# supply_dual_v0_11_a0fac544.net
KiCad netlist of a schematic drawn in EAGLE
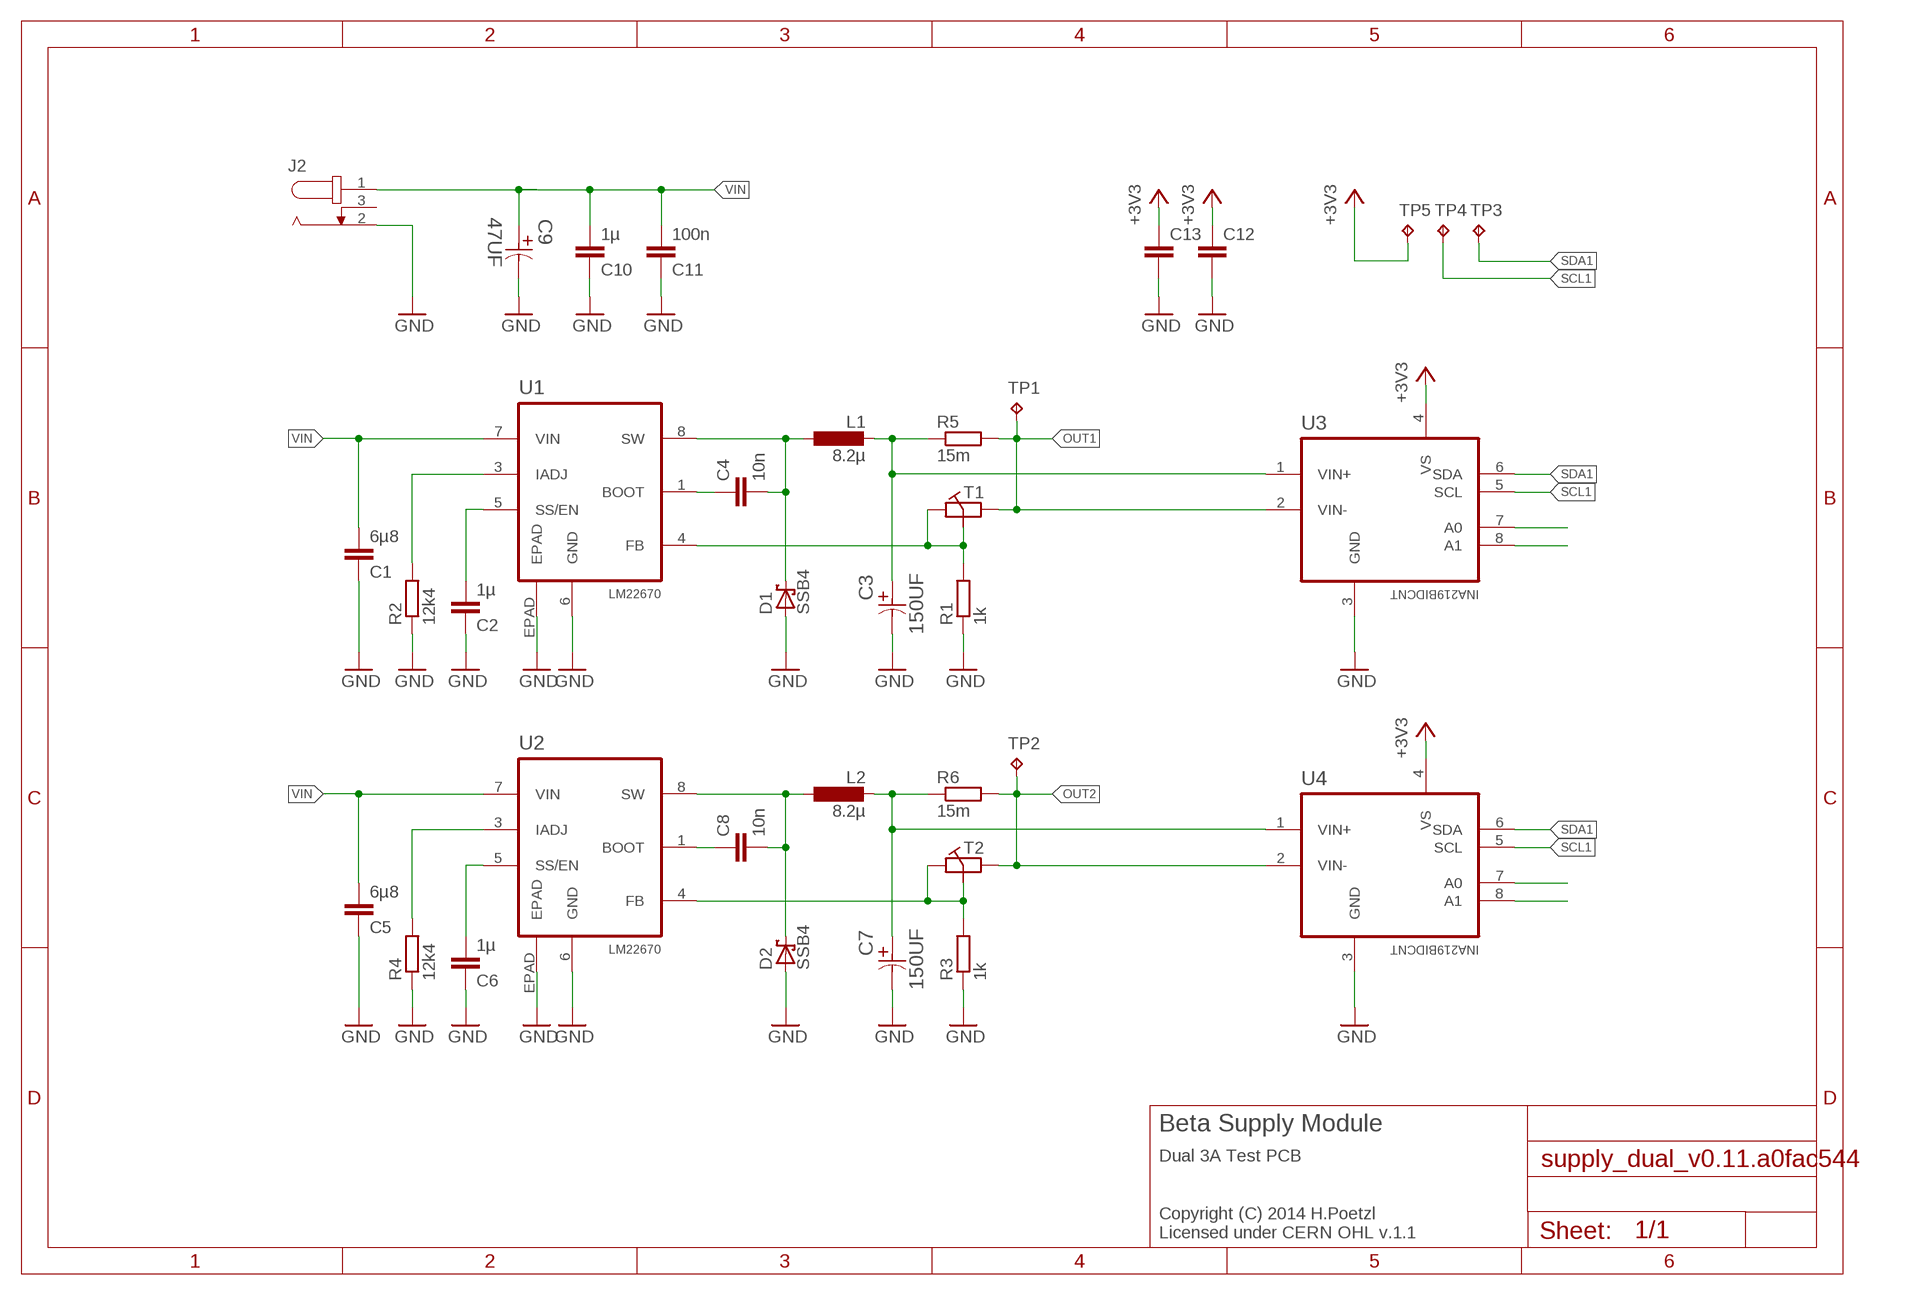
[diagram p0: schematic, sheet 1]

(export (version "E")
  (design (tool "Eeschema 10.0.6"))
  (components
    (comp (ref "C1")
      (value "6µ8")
      (footprint "eagle-import:C1210K")
      (libsource (lib "eagle-import") (part "C-EUC1210K"))
    )
    (comp (ref "C2")
      (value "1µ")
      (footprint "eagle-import:C0603K")
      (libsource (lib "eagle-import") (part "C-EUC0603K"))
    )
    (comp (ref "C3")
      (value "150UF")
      (footprint "eagle-import:CAPT7343X430N")
      (fields (field (name "MPN") "EEFCX0J151R"))
      (libsource (lib "eagle-import") (part "EEFCX0J151R"))
    )
    (comp (ref "C4")
      (value "10n")
      (footprint "eagle-import:C0603K")
      (libsource (lib "eagle-import") (part "C-EUC0603K"))
    )
    (comp (ref "C5")
      (value "6µ8")
      (footprint "eagle-import:C1210K")
      (libsource (lib "eagle-import") (part "C-EUC1210K"))
    )
    (comp (ref "C6")
      (value "1µ")
      (footprint "eagle-import:C0603K")
      (libsource (lib "eagle-import") (part "C-EUC0603K"))
    )
    (comp (ref "C7")
      (value "150UF")
      (footprint "eagle-import:CAPT7343X430N")
      (fields (field (name "MPN") "EEFCX0J151R"))
      (libsource (lib "eagle-import") (part "EEFCX0J151R"))
    )
    (comp (ref "C8")
      (value "10n")
      (footprint "eagle-import:C0603K")
      (libsource (lib "eagle-import") (part "C-EUC0603K"))
    )
    (comp (ref "C9")
      (value "47UF")
      (footprint "eagle-import:CAPAE660X610N")
      (fields (field (name "MPN") "EEE-FT1H470AP") (field (name "TOLERANCE") "±20 %"))
      (libsource (lib "eagle-import") (part "EEE--CASE-DFT1H470AP"))
    )
    (comp (ref "C10")
      (value "1µ")
      (footprint "eagle-import:C0805K")
      (libsource (lib "eagle-import") (part "C-EUC0805K"))
    )
    (comp (ref "C11")
      (value "100n")
      (footprint "eagle-import:C0603K")
      (libsource (lib "eagle-import") (part "C-EUC0603K"))
    )
    (comp (ref "C12")
      (value "C-EUC0402K")
      (footprint "eagle-import:C0402K")
      (libsource (lib "eagle-import") (part "C-EUC0402K"))
    )
    (comp (ref "C13")
      (value "C-EUC0402K")
      (footprint "eagle-import:C0402K")
      (libsource (lib "eagle-import") (part "C-EUC0402K"))
    )
    (comp (ref "D1")
      (value "SSB4")
      (footprint "eagle-import:DO-214AA")
      (libsource (lib "eagle-import") (part "SSB4"))
    )
    (comp (ref "D2")
      (value "SSB4")
      (footprint "eagle-import:DO-214AA")
      (libsource (lib "eagle-import") (part "SSB4"))
    )
    (comp (ref "J2")
      (value "JACK-PLUGDC12")
      (footprint "eagle-import:FC681485")
      (libsource (lib "eagle-import") (part "JACK-PLUGDC12"))
    )
    (comp (ref "L1")
      (value "8.2µ")
      (footprint "eagle-import:XAL50X0")
      (libsource (lib "eagle-import") (part "L-EUXAL50X0"))
    )
    (comp (ref "L2")
      (value "8.2µ")
      (footprint "eagle-import:XAL50X0")
      (libsource (lib "eagle-import") (part "L-EUXAL50X0"))
    )
    (comp (ref "R1")
      (value "1k")
      (footprint "eagle-import:R0402")
      (libsource (lib "eagle-import") (part "R-EU_R0402"))
    )
    (comp (ref "R2")
      (value "12k4")
      (footprint "eagle-import:R0402")
      (libsource (lib "eagle-import") (part "R-EU_R0402"))
    )
    (comp (ref "R3")
      (value "1k")
      (footprint "eagle-import:R0402")
      (libsource (lib "eagle-import") (part "R-EU_R0402"))
    )
    (comp (ref "R4")
      (value "12k4")
      (footprint "eagle-import:R0402")
      (libsource (lib "eagle-import") (part "R-EU_R0402"))
    )
    (comp (ref "R5")
      (value "15m")
      (footprint "eagle-import:R1210")
      (libsource (lib "eagle-import") (part "R-EU_R1210"))
    )
    (comp (ref "R6")
      (value "15m")
      (footprint "eagle-import:R1210")
      (libsource (lib "eagle-import") (part "R-EU_R1210"))
    )
    (comp (ref "T1")
      (value "PVZ2A")
      (footprint "eagle-import:TRIM-PVZ2A")
      (libsource (lib "eagle-import") (part "PVZ2A"))
    )
    (comp (ref "T2")
      (value "PVZ2A")
      (footprint "eagle-import:TRIM-PVZ2A")
      (libsource (lib "eagle-import") (part "PVZ2A"))
    )
    (comp (ref "TP1")
      (value "TPB1,27")
      (footprint "eagle-import:B1,27")
      (libsource (lib "eagle-import") (part "TPB1,27"))
    )
    (comp (ref "TP2")
      (value "TPB1,27")
      (footprint "eagle-import:B1,27")
      (libsource (lib "eagle-import") (part "TPB1,27"))
    )
    (comp (ref "TP3")
      (value "TPB1,27")
      (footprint "eagle-import:B1,27")
      (libsource (lib "eagle-import") (part "TPB1,27"))
    )
    (comp (ref "TP4")
      (value "TPB1,27")
      (footprint "eagle-import:B1,27")
      (libsource (lib "eagle-import") (part "TPB1,27"))
    )
    (comp (ref "TP5")
      (value "TPB1,27")
      (footprint "eagle-import:B1,27")
      (libsource (lib "eagle-import") (part "TPB1,27"))
    )
    (comp (ref "U1")
      (value "LM22670")
      (footprint "eagle-import:DDA0008B")
      (libsource (lib "eagle-import") (part "LM2267_123"))
    )
    (comp (ref "U2")
      (value "LM22670")
      (footprint "eagle-import:DDA0008B")
      (libsource (lib "eagle-import") (part "LM2267_123"))
    )
    (comp (ref "U3")
      (value "INA219BIDCNT")
      (footprint "eagle-import:SOT65P280X145-8N")
      (libsource (lib "eagle-import") (part "INA219BIDCNT"))
    )
    (comp (ref "U4")
      (value "INA219BIDCNT")
      (footprint "eagle-import:SOT65P280X145-8N")
      (libsource (lib "eagle-import") (part "INA219BIDCNT"))
    )
  )
  (nets
    (net (code "1") (name "+3V3") (class "Default")
      (node (ref "C12") (pin "1") (pinfunction "1_1") (pintype "passive"))
      (node (ref "C13") (pin "1") (pinfunction "1_1") (pintype "passive"))
      (node (ref "TP5") (pin "TP") (pinfunction "TP_TP") (pintype "input"))
      (node (ref "U3") (pin "4") (pinfunction "VS_4") (pintype "power_in"))
      (node (ref "U4") (pin "4") (pinfunction "VS_4") (pintype "power_in"))
    )
    (net (code "2") (name "GND") (class "Default")
      (node (ref "C1") (pin "1") (pinfunction "1_1") (pintype "passive"))
      (node (ref "C10") (pin "1") (pinfunction "1_1") (pintype "passive"))
      (node (ref "C11") (pin "1") (pinfunction "1_1") (pintype "passive"))
      (node (ref "C12") (pin "2") (pinfunction "2_2") (pintype "passive"))
      (node (ref "C13") (pin "2") (pinfunction "2_2") (pintype "passive"))
      (node (ref "C2") (pin "1") (pinfunction "1_1") (pintype "passive"))
      (node (ref "C3") (pin "2") (pinfunction "2_2") (pintype "passive"))
      (node (ref "C5") (pin "1") (pinfunction "1_1") (pintype "passive"))
      (node (ref "C6") (pin "1") (pinfunction "1_1") (pintype "passive"))
      (node (ref "C7") (pin "2") (pinfunction "2_2") (pintype "passive"))
      (node (ref "C9") (pin "2") (pinfunction "2_2") (pintype "passive"))
      (node (ref "D1") (pin "A") (pinfunction "A_A") (pintype "passive"))
      (node (ref "D2") (pin "A") (pinfunction "A_A") (pintype "passive"))
      (node (ref "J2") (pin "2") (pinfunction "2_2") (pintype "passive"))
      (node (ref "R1") (pin "1") (pinfunction "1_1") (pintype "passive"))
      (node (ref "R2") (pin "1") (pinfunction "1_1") (pintype "passive"))
      (node (ref "R3") (pin "1") (pinfunction "1_1") (pintype "passive"))
      (node (ref "R4") (pin "1") (pinfunction "1_1") (pintype "passive"))
      (node (ref "U1") (pin "6") (pinfunction "GND_6") (pintype "power_in"))
      (node (ref "U1") (pin "EPAD") (pinfunction "EPAD_EPAD") (pintype "power_in"))
      (node (ref "U2") (pin "6") (pinfunction "GND_6") (pintype "power_in"))
      (node (ref "U2") (pin "EPAD") (pinfunction "EPAD_EPAD") (pintype "power_in"))
      (node (ref "U3") (pin "3") (pinfunction "GND_3") (pintype "passive"))
      (node (ref "U4") (pin "3") (pinfunction "GND_3") (pintype "passive"))
    )
    (net (code "3") (name "Net-(T1-B)") (class "Default")
      (node (ref "R1") (pin "2") (pinfunction "2_2") (pintype "passive"))
      (node (ref "T1") (pin "2") (pinfunction "B_2") (pintype "bidirectional"))
      (node (ref "T1") (pin "3") (pinfunction "C_3") (pintype "bidirectional"))
      (node (ref "U1") (pin "4") (pinfunction "FB_4") (pintype "input"))
    )
    (net (code "4") (name "Net-(T2-B)") (class "Default")
      (node (ref "R3") (pin "2") (pinfunction "2_2") (pintype "passive"))
      (node (ref "T2") (pin "2") (pinfunction "B_2") (pintype "bidirectional"))
      (node (ref "T2") (pin "3") (pinfunction "C_3") (pintype "bidirectional"))
      (node (ref "U2") (pin "4") (pinfunction "FB_4") (pintype "input"))
    )
    (net (code "5") (name "Net-(U1-BOOT)") (class "Default")
      (node (ref "C4") (pin "1") (pinfunction "1_1") (pintype "passive"))
      (node (ref "U1") (pin "1") (pinfunction "BOOT_1") (pintype "power_in"))
    )
    (net (code "6") (name "Net-(U1-IADJ)") (class "Default")
      (node (ref "R2") (pin "2") (pinfunction "2_2") (pintype "passive"))
      (node (ref "U1") (pin "3") (pinfunction "IADJ_3") (pintype "input"))
    )
    (net (code "7") (name "Net-(U1-SS{slash}EN)") (class "Default")
      (node (ref "C2") (pin "2") (pinfunction "2_2") (pintype "passive"))
      (node (ref "U1") (pin "5") (pinfunction "SS/EN_5") (pintype "input"))
    )
    (net (code "8") (name "Net-(U1-SW)") (class "Default")
      (node (ref "C4") (pin "2") (pinfunction "2_2") (pintype "passive"))
      (node (ref "D1") (pin "C") (pinfunction "C_C") (pintype "passive"))
      (node (ref "L1") (pin "1") (pinfunction "1_1") (pintype "passive"))
      (node (ref "U1") (pin "8") (pinfunction "SW_8") (pintype "power_in"))
    )
    (net (code "9") (name "Net-(U2-BOOT)") (class "Default")
      (node (ref "C8") (pin "1") (pinfunction "1_1") (pintype "passive"))
      (node (ref "U2") (pin "1") (pinfunction "BOOT_1") (pintype "power_in"))
    )
    (net (code "10") (name "Net-(U2-IADJ)") (class "Default")
      (node (ref "R4") (pin "2") (pinfunction "2_2") (pintype "passive"))
      (node (ref "U2") (pin "3") (pinfunction "IADJ_3") (pintype "input"))
    )
    (net (code "11") (name "Net-(U2-SS{slash}EN)") (class "Default")
      (node (ref "C6") (pin "2") (pinfunction "2_2") (pintype "passive"))
      (node (ref "U2") (pin "5") (pinfunction "SS/EN_5") (pintype "input"))
    )
    (net (code "12") (name "Net-(U2-SW)") (class "Default")
      (node (ref "C8") (pin "2") (pinfunction "2_2") (pintype "passive"))
      (node (ref "D2") (pin "C") (pinfunction "C_C") (pintype "passive"))
      (node (ref "L2") (pin "1") (pinfunction "1_1") (pintype "passive"))
      (node (ref "U2") (pin "8") (pinfunction "SW_8") (pintype "power_in"))
    )
    (net (code "13") (name "Net-(U3-VIN+)") (class "Default")
      (node (ref "C3") (pin "1") (pinfunction "1_1") (pintype "passive"))
      (node (ref "L1") (pin "2") (pinfunction "2_2") (pintype "passive"))
      (node (ref "R5") (pin "1") (pinfunction "1_1") (pintype "passive"))
      (node (ref "U3") (pin "1") (pinfunction "VIN+_1") (pintype "power_in"))
    )
    (net (code "14") (name "Net-(U4-VIN+)") (class "Default")
      (node (ref "C7") (pin "1") (pinfunction "1_1") (pintype "passive"))
      (node (ref "L2") (pin "2") (pinfunction "2_2") (pintype "passive"))
      (node (ref "R6") (pin "1") (pinfunction "1_1") (pintype "passive"))
      (node (ref "U4") (pin "1") (pinfunction "VIN+_1") (pintype "power_in"))
    )
    (net (code "15") (name "OUT1") (class "Default")
      (node (ref "R5") (pin "2") (pinfunction "2_2") (pintype "passive"))
      (node (ref "T1") (pin "1") (pinfunction "A_1") (pintype "bidirectional"))
      (node (ref "TP1") (pin "TP") (pinfunction "TP_TP") (pintype "input"))
      (node (ref "U3") (pin "2") (pinfunction "VIN-_2") (pintype "power_in"))
    )
    (net (code "16") (name "OUT2") (class "Default")
      (node (ref "R6") (pin "2") (pinfunction "2_2") (pintype "passive"))
      (node (ref "T2") (pin "1") (pinfunction "A_1") (pintype "bidirectional"))
      (node (ref "TP2") (pin "TP") (pinfunction "TP_TP") (pintype "input"))
      (node (ref "U4") (pin "2") (pinfunction "VIN-_2") (pintype "power_in"))
    )
    (net (code "17") (name "SCL1") (class "Default")
      (node (ref "TP4") (pin "TP") (pinfunction "TP_TP") (pintype "input"))
      (node (ref "U3") (pin "5") (pinfunction "SCL_5") (pintype "input"))
      (node (ref "U4") (pin "5") (pinfunction "SCL_5") (pintype "input"))
    )
    (net (code "18") (name "SDA1") (class "Default")
      (node (ref "TP3") (pin "TP") (pinfunction "TP_TP") (pintype "input"))
      (node (ref "U3") (pin "6") (pinfunction "SDA_6") (pintype "bidirectional"))
      (node (ref "U4") (pin "6") (pinfunction "SDA_6") (pintype "bidirectional"))
    )
    (net (code "19") (name "VIN") (class "Default")
      (node (ref "C1") (pin "2") (pinfunction "2_2") (pintype "passive"))
      (node (ref "C10") (pin "2") (pinfunction "2_2") (pintype "passive"))
      (node (ref "C11") (pin "2") (pinfunction "2_2") (pintype "passive"))
      (node (ref "C5") (pin "2") (pinfunction "2_2") (pintype "passive"))
      (node (ref "C9") (pin "1") (pinfunction "1_1") (pintype "passive"))
      (node (ref "J2") (pin "1") (pinfunction "1_1") (pintype "passive"))
      (node (ref "U1") (pin "7") (pinfunction "VIN_7") (pintype "power_in"))
      (node (ref "U2") (pin "7") (pinfunction "VIN_7") (pintype "power_in"))
    )
    (net (code "20") (name "unconnected-(J2-Pad3)") (class "Default")
      (node (ref "J2") (pin "3") (pinfunction "3_3") (pintype "passive"))
    )
    (net (code "21") (name "unconnected-(U3-A0-Pad7)") (class "Default")
      (node (ref "U3") (pin "7") (pinfunction "A0_7") (pintype "input"))
    )
    (net (code "22") (name "unconnected-(U3-A1-Pad8)") (class "Default")
      (node (ref "U3") (pin "8") (pinfunction "A1_8") (pintype "input"))
    )
    (net (code "23") (name "unconnected-(U4-A0-Pad7)") (class "Default")
      (node (ref "U4") (pin "7") (pinfunction "A0_7") (pintype "input"))
    )
    (net (code "24") (name "unconnected-(U4-A1-Pad8)") (class "Default")
      (node (ref "U4") (pin "8") (pinfunction "A1_8") (pintype "input"))
    )
  )
)
